# magnetoV3_0.net
KiCad netlist of a schematic drawn in EAGLE
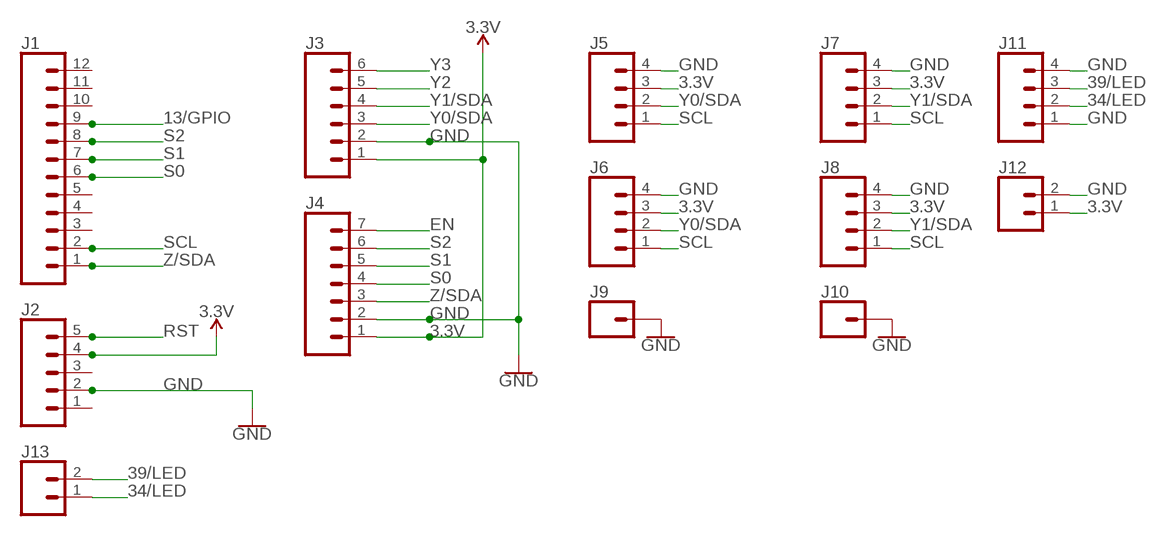
[diagram p0: schematic, sheet 1]

(export (version "E")
  (design (tool "Eeschema 10.0.6"))
  (components
    (comp (ref "J1")
      (value "CONN_12")
      (footprint "eagle-import:1X12")
      (libsource (lib "eagle-import") (part "CONN_12"))
    )
    (comp (ref "J2")
      (value "CONN_05")
      (footprint "eagle-import:1X05")
      (libsource (lib "eagle-import") (part "CONN_05"))
    )
    (comp (ref "J3")
      (value "CONN_06SILK_FEMALE_PTH")
      (footprint "eagle-import:1X06")
      (libsource (lib "eagle-import") (part "CONN_06SILK_FEMALE_PTH"))
    )
    (comp (ref "J4")
      (value "CONN_07")
      (footprint "eagle-import:1X07")
      (libsource (lib "eagle-import") (part "CONN_07"))
    )
    (comp (ref "J5")
      (value "CONN_04")
      (footprint "eagle-import:1X04")
      (libsource (lib "eagle-import") (part "CONN_04"))
    )
    (comp (ref "J6")
      (value "CONN_04")
      (footprint "eagle-import:1X04")
      (libsource (lib "eagle-import") (part "CONN_04"))
    )
    (comp (ref "J7")
      (value "CONN_04")
      (footprint "eagle-import:1X04")
      (libsource (lib "eagle-import") (part "CONN_04"))
    )
    (comp (ref "J8")
      (value "CONN_04")
      (footprint "eagle-import:1X04")
      (libsource (lib "eagle-import") (part "CONN_04"))
    )
    (comp (ref "J9")
      (value "CONN_01")
      (footprint "eagle-import:1X01")
      (libsource (lib "eagle-import") (part "CONN_01"))
    )
    (comp (ref "J10")
      (value "CONN_01")
      (footprint "eagle-import:1X01")
      (libsource (lib "eagle-import") (part "CONN_01"))
    )
    (comp (ref "J11")
      (value "CONN_04")
      (footprint "eagle-import:1X04")
      (libsource (lib "eagle-import") (part "CONN_04"))
    )
    (comp (ref "J12")
      (value "CONN_02")
      (footprint "eagle-import:1X02")
      (libsource (lib "eagle-import") (part "CONN_02"))
    )
    (comp (ref "J13")
      (value "CONN_02")
      (footprint "eagle-import:1X02")
      (libsource (lib "eagle-import") (part "CONN_02"))
    )
  )
  (nets
    (net (code "1") (name "/13{slash}GPIO") (class "Default")
      (node (ref "J1") (pin "9") (pinfunction "9_9") (pintype "passive"))
    )
    (net (code "2") (name "/34{slash}LED") (class "Default")
      (node (ref "J11") (pin "2") (pinfunction "2_2") (pintype "passive"))
      (node (ref "J13") (pin "1") (pinfunction "1_1") (pintype "passive"))
    )
    (net (code "3") (name "/39{slash}LED") (class "Default")
      (node (ref "J11") (pin "3") (pinfunction "3_3") (pintype "passive"))
      (node (ref "J13") (pin "2") (pinfunction "2_2") (pintype "passive"))
    )
    (net (code "4") (name "/EN") (class "Default")
      (node (ref "J4") (pin "7") (pinfunction "7_7") (pintype "passive"))
    )
    (net (code "5") (name "/RST") (class "Default")
      (node (ref "J2") (pin "5") (pinfunction "5_5") (pintype "passive"))
    )
    (net (code "6") (name "/S0") (class "Default")
      (node (ref "J1") (pin "6") (pinfunction "6_6") (pintype "passive"))
      (node (ref "J4") (pin "4") (pinfunction "4_4") (pintype "passive"))
    )
    (net (code "7") (name "/S1") (class "Default")
      (node (ref "J1") (pin "7") (pinfunction "7_7") (pintype "passive"))
      (node (ref "J4") (pin "5") (pinfunction "5_5") (pintype "passive"))
    )
    (net (code "8") (name "/S2") (class "Default")
      (node (ref "J1") (pin "8") (pinfunction "8_8") (pintype "passive"))
      (node (ref "J4") (pin "6") (pinfunction "6_6") (pintype "passive"))
    )
    (net (code "9") (name "/SCL") (class "Default")
      (node (ref "J1") (pin "2") (pinfunction "2_2") (pintype "passive"))
      (node (ref "J5") (pin "1") (pinfunction "1_1") (pintype "passive"))
      (node (ref "J6") (pin "1") (pinfunction "1_1") (pintype "passive"))
      (node (ref "J7") (pin "1") (pinfunction "1_1") (pintype "passive"))
      (node (ref "J8") (pin "1") (pinfunction "1_1") (pintype "passive"))
    )
    (net (code "10") (name "/Y0{slash}SDA") (class "Default")
      (node (ref "J3") (pin "3") (pinfunction "3_3") (pintype "passive"))
      (node (ref "J5") (pin "2") (pinfunction "2_2") (pintype "passive"))
      (node (ref "J6") (pin "2") (pinfunction "2_2") (pintype "passive"))
    )
    (net (code "11") (name "/Y1{slash}SDA") (class "Default")
      (node (ref "J3") (pin "4") (pinfunction "4_4") (pintype "passive"))
      (node (ref "J7") (pin "2") (pinfunction "2_2") (pintype "passive"))
      (node (ref "J8") (pin "2") (pinfunction "2_2") (pintype "passive"))
    )
    (net (code "12") (name "/Y2") (class "Default")
      (node (ref "J3") (pin "5") (pinfunction "5_5") (pintype "passive"))
    )
    (net (code "13") (name "/Y3") (class "Default")
      (node (ref "J3") (pin "6") (pinfunction "6_6") (pintype "passive"))
    )
    (net (code "14") (name "/Z{slash}SDA") (class "Default")
      (node (ref "J1") (pin "1") (pinfunction "1_1") (pintype "passive"))
      (node (ref "J4") (pin "3") (pinfunction "3_3") (pintype "passive"))
    )
    (net (code "15") (name "3.3V") (class "Default")
      (node (ref "J12") (pin "1") (pinfunction "1_1") (pintype "passive"))
      (node (ref "J2") (pin "4") (pinfunction "4_4") (pintype "passive"))
      (node (ref "J3") (pin "1") (pinfunction "1_1") (pintype "passive"))
      (node (ref "J4") (pin "1") (pinfunction "1_1") (pintype "passive"))
      (node (ref "J5") (pin "3") (pinfunction "3_3") (pintype "passive"))
      (node (ref "J6") (pin "3") (pinfunction "3_3") (pintype "passive"))
      (node (ref "J7") (pin "3") (pinfunction "3_3") (pintype "passive"))
      (node (ref "J8") (pin "3") (pinfunction "3_3") (pintype "passive"))
    )
    (net (code "16") (name "GND") (class "Default")
      (node (ref "J10") (pin "1") (pinfunction "1_1") (pintype "passive"))
      (node (ref "J11") (pin "1") (pinfunction "1_1") (pintype "passive"))
      (node (ref "J11") (pin "4") (pinfunction "4_4") (pintype "passive"))
      (node (ref "J12") (pin "2") (pinfunction "2_2") (pintype "passive"))
      (node (ref "J2") (pin "2") (pinfunction "2_2") (pintype "passive"))
      (node (ref "J3") (pin "2") (pinfunction "2_2") (pintype "passive"))
      (node (ref "J4") (pin "2") (pinfunction "2_2") (pintype "passive"))
      (node (ref "J5") (pin "4") (pinfunction "4_4") (pintype "passive"))
      (node (ref "J6") (pin "4") (pinfunction "4_4") (pintype "passive"))
      (node (ref "J7") (pin "4") (pinfunction "4_4") (pintype "passive"))
      (node (ref "J8") (pin "4") (pinfunction "4_4") (pintype "passive"))
      (node (ref "J9") (pin "1") (pinfunction "1_1") (pintype "passive"))
    )
    (net (code "17") (name "unconnected-(J1-Pad3)") (class "Default")
      (node (ref "J1") (pin "3") (pinfunction "3_3") (pintype "passive"))
    )
    (net (code "18") (name "unconnected-(J1-Pad4)") (class "Default")
      (node (ref "J1") (pin "4") (pinfunction "4_4") (pintype "passive"))
    )
    (net (code "19") (name "unconnected-(J1-Pad5)") (class "Default")
      (node (ref "J1") (pin "5") (pinfunction "5_5") (pintype "passive"))
    )
    (net (code "20") (name "unconnected-(J1-Pad10)") (class "Default")
      (node (ref "J1") (pin "10") (pinfunction "10_10") (pintype "passive"))
    )
    (net (code "21") (name "unconnected-(J1-Pad11)") (class "Default")
      (node (ref "J1") (pin "11") (pinfunction "11_11") (pintype "passive"))
    )
    (net (code "22") (name "unconnected-(J1-Pad12)") (class "Default")
      (node (ref "J1") (pin "12") (pinfunction "12_12") (pintype "passive"))
    )
    (net (code "23") (name "unconnected-(J2-Pad1)") (class "Default")
      (node (ref "J2") (pin "1") (pinfunction "1_1") (pintype "passive"))
    )
    (net (code "24") (name "unconnected-(J2-Pad3)") (class "Default")
      (node (ref "J2") (pin "3") (pinfunction "3_3") (pintype "passive"))
    )
  )
)
